# DB4100_DRV.net
KiCad netlist of a schematic drawn in Altium Designer
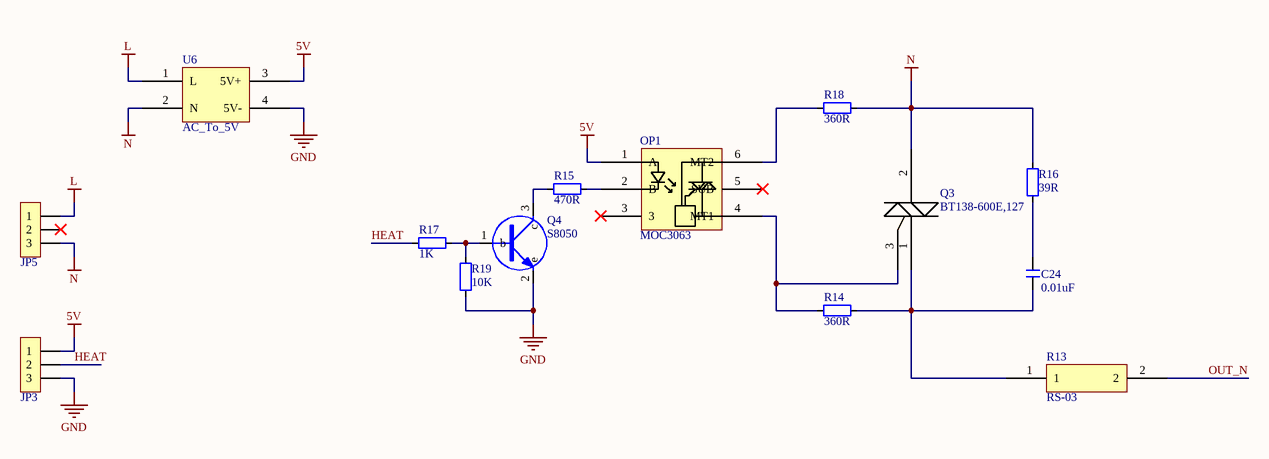
[diagram p0: DB4100_DRV.SchDoc]

(export (version "E")
  (design (tool "Eeschema 10.0.6"))
  (components
    (comp (ref "C24")
      (value "0.01uF")
      (footprint "MLCC5.08-A")
      (description "独石电容")
      (fields (field (name "版权归属") "源创客"))
      (libsource (lib "电容") (part "C-MLCC"))
    )
    (comp (ref "JP3")
      (value "HDR-1X3")
      (footprint "XH2.54-3P")
      (description "3P接插件")
      (fields (field (name "版权归属") "源创客"))
      (libsource (lib "排针-排母") (part "Header 3"))
    )
    (comp (ref "JP5")
      (value "HDR-1X3")
      (footprint "VH3.96-3PWB")
      (description "3P接插件")
      (fields (field (name "版权归属") "源创客"))
      (libsource (lib "排针-排母") (part "Header 3"))
    )
    (comp (ref "OP1")
      (value "MOC3063")
      (footprint "MOC3063")
      (description "双向可控硅")
      (libsource (lib "常用芯片") (part "MOC3063"))
    )
    (comp (ref "Q3")
      (value "BT138-600E,127")
      (footprint "BT138-600E,127")
      (description "晶闸管(可控硅)/模块")
      (libsource (lib "二极管-整流桥") (part "BT138-600E,127"))
    )
    (comp (ref "Q4") (value "S8050") (footprint "SOT23-3L") (libsource (lib "三极管") (part "NPN")))
    (comp (ref "R13")
      (value "RS-03")
      (footprint "RS-03")
      (description "电吹风热保护器")
      (libsource (lib "模块器件") (part "RS-03"))
    )
    (comp (ref "R14")
      (value "360R")
      (footprint "R 1206")
      (description "贴片电阻")
      (fields (field (name "版权归属") "源创客"))
      (libsource (lib "") (part "R_2"))
    )
    (comp (ref "R15")
      (value "470R")
      (footprint "R 0603")
      (description "贴片电阻")
      (fields (field (name "版权归属") "源创客"))
      (libsource (lib "电阻") (part "R"))
    )
    (comp (ref "R16")
      (value "39R")
      (footprint "R 1206")
      (description "贴片电阻")
      (fields (field (name "版权归属") "源创客"))
      (libsource (lib "") (part "R_1"))
    )
    (comp (ref "R17")
      (value "1K")
      (footprint "R 0603")
      (description "贴片电阻")
      (fields (field (name "版权归属") "源创客"))
      (libsource (lib "电阻") (part "R"))
    )
    (comp (ref "R18")
      (value "360R")
      (footprint "R 1206")
      (description "贴片电阻")
      (fields (field (name "版权归属") "源创客"))
      (libsource (lib "") (part "R_2"))
    )
    (comp (ref "R19")
      (value "10K")
      (footprint "R 0603")
      (description "贴片电阻")
      (fields (field (name "版权归属") "源创客"))
      (libsource (lib "") (part "R_2"))
    )
    (comp (ref "U6")
      (value "AC_To_5V")
      (footprint "ACTo5v")
      (description "220V转5V降压模块")
      (libsource (lib "变压器") (part "AC_To_5V"))
    )
  )
  (nets
    (net (code "1") (name "/HEAT") (class "Default")
      (node (ref "JP3") (pin "2") (pinfunction "2_2") (pintype "passive"))
      (node (ref "R17") (pin "1") (pinfunction "1_1") (pintype "passive"))
    )
    (net (code "2") (name "/OUT_N") (class "Default")
      (node (ref "R13") (pin "2") (pinfunction "2_2") (pintype "passive"))
    )
    (net (code "3") (name "5V") (class "Default")
      (node (ref "JP3") (pin "1") (pinfunction "1_1") (pintype "passive"))
      (node (ref "OP1") (pin "1") (pinfunction "A_1") (pintype "passive"))
      (node (ref "U6") (pin "3") (pinfunction "5V+_3") (pintype "passive"))
    )
    (net (code "4") (name "GND") (class "Default")
      (node (ref "JP3") (pin "3") (pinfunction "3_3") (pintype "passive"))
      (node (ref "Q4") (pin "2") (pinfunction "e_2") (pintype "passive"))
      (node (ref "R19") (pin "1") (pinfunction "1_1") (pintype "passive"))
      (node (ref "U6") (pin "4") (pinfunction "5V-_4") (pintype "passive"))
    )
    (net (code "5") (name "L") (class "Default")
      (node (ref "JP5") (pin "1") (pinfunction "1_1") (pintype "passive"))
      (node (ref "U6") (pin "1") (pinfunction "L_1") (pintype "passive"))
    )
    (net (code "6") (name "N") (class "Default")
      (node (ref "JP5") (pin "3") (pinfunction "3_3") (pintype "passive"))
      (node (ref "Q3") (pin "2") (pinfunction "2_2") (pintype "passive"))
      (node (ref "R16") (pin "1") (pinfunction "1_1") (pintype "passive"))
      (node (ref "R18") (pin "2") (pinfunction "2_2") (pintype "passive"))
      (node (ref "U6") (pin "2") (pinfunction "N_2") (pintype "passive"))
    )
    (net (code "7") (name "Net-(C24-Pad1)") (class "Default")
      (node (ref "C24") (pin "1") (pinfunction "1_1") (pintype "passive"))
      (node (ref "R16") (pin "2") (pinfunction "2_2") (pintype "passive"))
    )
    (net (code "8") (name "Net-(C24-Pad2)") (class "Default")
      (node (ref "C24") (pin "2") (pinfunction "2_2") (pintype "passive"))
      (node (ref "Q3") (pin "1") (pinfunction "1_1") (pintype "passive"))
      (node (ref "R13") (pin "1") (pinfunction "1_1") (pintype "passive"))
      (node (ref "R14") (pin "2") (pinfunction "2_2") (pintype "passive"))
    )
    (net (code "9") (name "Net-(OP1-B)") (class "Default")
      (node (ref "OP1") (pin "2") (pinfunction "B_2") (pintype "passive"))
      (node (ref "R15") (pin "2") (pinfunction "2_2") (pintype "passive"))
    )
    (net (code "10") (name "Net-(OP1-MT1)") (class "Default")
      (node (ref "OP1") (pin "4") (pinfunction "MT1_4") (pintype "passive"))
      (node (ref "Q3") (pin "3") (pinfunction "3_3") (pintype "passive"))
      (node (ref "R14") (pin "1") (pinfunction "1_1") (pintype "passive"))
    )
    (net (code "11") (name "Net-(OP1-MT2)") (class "Default")
      (node (ref "OP1") (pin "6") (pinfunction "MT2_6") (pintype "passive"))
      (node (ref "R18") (pin "1") (pinfunction "1_1") (pintype "passive"))
    )
    (net (code "12") (name "Net-(Q4-b)") (class "Default")
      (node (ref "Q4") (pin "1") (pinfunction "b_1") (pintype "passive"))
      (node (ref "R17") (pin "2") (pinfunction "2_2") (pintype "passive"))
      (node (ref "R19") (pin "2") (pinfunction "2_2") (pintype "passive"))
    )
    (net (code "13") (name "Net-(Q4-c)") (class "Default")
      (node (ref "Q4") (pin "3") (pinfunction "c_3") (pintype "passive"))
      (node (ref "R15") (pin "1") (pinfunction "1_1") (pintype "passive"))
    )
    (net (code "14") (name "unconnected-(JP5-Pad2)") (class "Default")
      (node (ref "JP5") (pin "2") (pinfunction "2_2") (pintype "passive+no_connect"))
    )
    (net (code "15") (name "unconnected-(OP1-Pad3)") (class "Default")
      (node (ref "OP1") (pin "3") (pinfunction "3_3") (pintype "passive+no_connect"))
    )
    (net (code "16") (name "unconnected-(OP1-SUB-Pad5)") (class "Default")
      (node (ref "OP1") (pin "5") (pinfunction "SUB_5") (pintype "passive+no_connect"))
    )
  )
)
